# VGA.net
KiCad netlist of a schematic drawn in Altium Designer
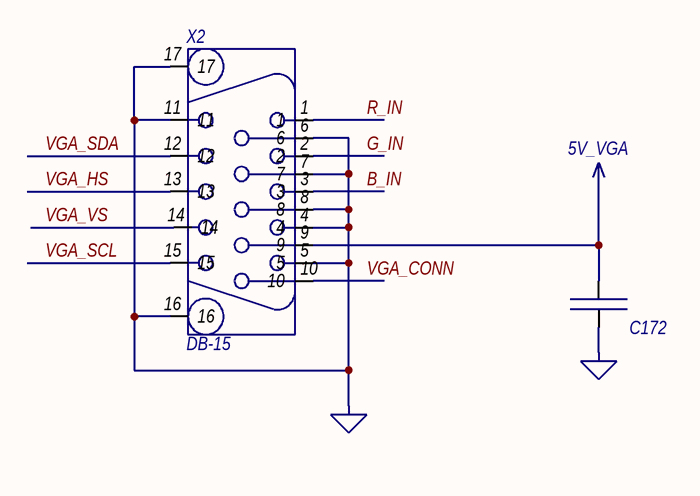
[diagram p0: VGA.SchDoc]

(export (version "E")
  (design (tool "Eeschema 10.0.6"))
  (components
    (comp (ref "C172")
      (value "Capacitor")
      (footprint "cap_electro_13")
      (libsource (lib "31_lib") (part "Capacitor"))
    )
    (comp (ref "X2")
      (value "DB-15")
      (footprint "31_lib:VGA")
      (libsource (lib "31_lib") (part "VGA_connector"))
    )
  )
  (nets
    (net (code "1") (name "/B_IN") (class "Default")
      (node (ref "X2") (pin "3") (pinfunction "3_3") (pintype "passive"))
    )
    (net (code "2") (name "/G_IN") (class "Default")
      (node (ref "X2") (pin "2") (pinfunction "2_2") (pintype "passive"))
    )
    (net (code "3") (name "/R_IN") (class "Default")
      (node (ref "X2") (pin "1") (pinfunction "1_1") (pintype "passive"))
    )
    (net (code "4") (name "/VGA_CONN") (class "Default")
      (node (ref "X2") (pin "10") (pinfunction "10_10") (pintype "passive"))
    )
    (net (code "5") (name "/VGA_HS") (class "Default")
      (node (ref "X2") (pin "13") (pinfunction "13_13") (pintype "passive"))
    )
    (net (code "6") (name "/VGA_SCL") (class "Default")
      (node (ref "X2") (pin "15") (pinfunction "15_15") (pintype "passive"))
    )
    (net (code "7") (name "/VGA_SDA") (class "Default")
      (node (ref "X2") (pin "12") (pinfunction "12_12") (pintype "passive"))
    )
    (net (code "8") (name "/VGA_VS") (class "Default")
      (node (ref "X2") (pin "14") (pinfunction "14_14") (pintype "passive"))
    )
    (net (code "9") (name "5V_VGA") (class "Default")
      (node (ref "C172") (pin "2") (pinfunction "2_2") (pintype "passive"))
      (node (ref "X2") (pin "9") (pinfunction "9_9") (pintype "passive"))
    )
    (net (code "10") (name "GND") (class "Default")
      (node (ref "C172") (pin "1") (pinfunction "1_1") (pintype "passive"))
      (node (ref "X2") (pin "11") (pinfunction "11_11") (pintype "passive"))
      (node (ref "X2") (pin "16") (pinfunction "16_16") (pintype "passive"))
      (node (ref "X2") (pin "17") (pinfunction "17_17") (pintype "passive"))
      (node (ref "X2") (pin "4") (pinfunction "4_4") (pintype "passive"))
      (node (ref "X2") (pin "5") (pinfunction "5_5") (pintype "passive"))
      (node (ref "X2") (pin "6") (pinfunction "6_6") (pintype "passive"))
      (node (ref "X2") (pin "7") (pinfunction "7_7") (pintype "passive"))
      (node (ref "X2") (pin "8") (pinfunction "8_8") (pintype "passive"))
    )
  )
)
